# 3V3_REG.net
KiCad netlist of a schematic drawn in Altium Designer
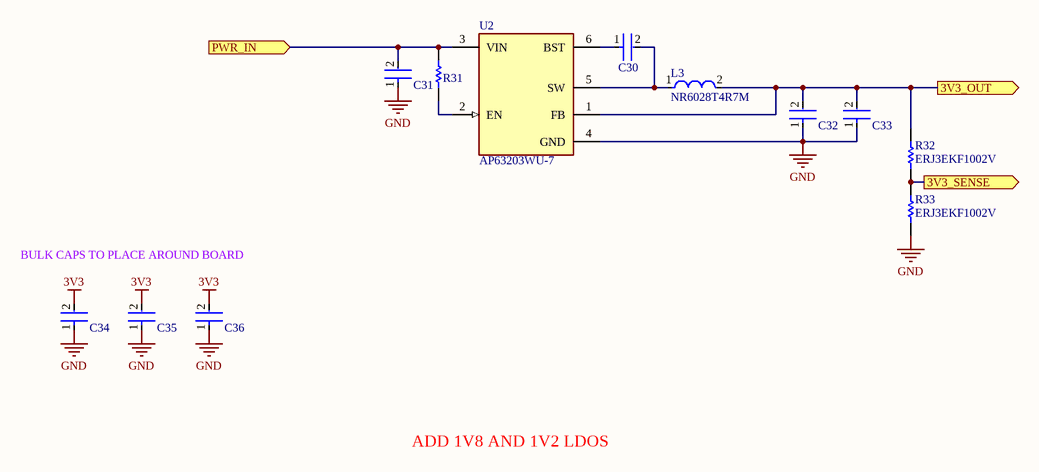
[diagram p0: 3V3_REG.SchDoc]

(export (version "E")
  (design (tool "Eeschema 10.0.6"))
  (components
    (comp (ref "C30")
      (value "C1005X7R1H104K050BB")
      (footprint "FP-C1005-050-0_05-IPC_C")
      (description "Multilayer Ceramic Capacitors 100nF ±10% 50V X7R SMD 0402")
      (fields (field (name "VOLTAGE") "50V") (field (name "TOLERANCE") "10%"))
      (libsource (lib "Altium Content Vault") (part "b4654b650e69147ec39a6b967a45e02"))
    )
    (comp (ref "C31")
      (value "GRM21BR61E226ME44L")
      (footprint "FP-GRM21B-0_2-e0_2_0_7-IPC_B")
      (description "Chip Multilayer Ceramic Capacitors for General Purpose, 0805, 22uF, X5R, 15%, 20%, 25V")
      (fields (field (name "TOLERANCE") "20%") (field (name "VOLTAGE") "25V"))
      (libsource (lib "Altium Content Vault") (part "b4654b650e69147ec39a6b967a45e02"))
    )
    (comp (ref "C32")
      (value "GRM21BR61E226ME44L")
      (footprint "FP-GRM21B-0_2-e0_2_0_7-IPC_B")
      (description "Chip Multilayer Ceramic Capacitors for General Purpose, 0805, 22uF, X5R, 15%, 20%, 25V")
      (fields (field (name "TOLERANCE") "20%") (field (name "VOLTAGE") "25V"))
      (libsource (lib "Altium Content Vault") (part "b4654b650e69147ec39a6b967a45e02"))
    )
    (comp (ref "C33")
      (value "GRM21BR61E226ME44L")
      (footprint "FP-GRM21B-0_2-e0_2_0_7-IPC_B")
      (description "Chip Multilayer Ceramic Capacitors for General Purpose, 0805, 22uF, X5R, 15%, 20%, 25V")
      (fields (field (name "TOLERANCE") "20%") (field (name "VOLTAGE") "25V"))
      (libsource (lib "Altium Content Vault") (part "b4654b650e69147ec39a6b967a45e02"))
    )
    (comp (ref "C34")
      (value "GRM21BR61E226ME44L")
      (footprint "FP-GRM21B-0_2-e0_2_0_7-IPC_B")
      (description "Chip Multilayer Ceramic Capacitors for General Purpose, 0805, 22uF, X5R, 15%, 20%, 25V")
      (fields (field (name "TOLERANCE") "20%") (field (name "VOLTAGE") "25V"))
      (libsource (lib "Altium Content Vault") (part "b4654b650e69147ec39a6b967a45e02"))
    )
    (comp (ref "C35")
      (value "GRM21BR61E226ME44L")
      (footprint "FP-GRM21B-0_2-e0_2_0_7-IPC_B")
      (description "Chip Multilayer Ceramic Capacitors for General Purpose, 0805, 22uF, X5R, 15%, 20%, 25V")
      (fields (field (name "TOLERANCE") "20%") (field (name "VOLTAGE") "25V"))
      (libsource (lib "Altium Content Vault") (part "b4654b650e69147ec39a6b967a45e02"))
    )
    (comp (ref "C36")
      (value "GRM21BR61E226ME44L")
      (footprint "FP-GRM21B-0_2-e0_2_0_7-IPC_B")
      (description "Chip Multilayer Ceramic Capacitors for General Purpose, 0805, 22uF, X5R, 15%, 20%, 25V")
      (fields (field (name "TOLERANCE") "20%") (field (name "VOLTAGE") "25V"))
      (libsource (lib "Altium Content Vault") (part "b4654b650e69147ec39a6b967a45e02"))
    )
    (comp (ref "L3")
      (value "NR6028T4R7M")
      (footprint "FP-NR6028-MFG")
      (description "SMD Power Inductors 4.7uH ±20% 2.7A 40.3mΩ")
      (fields (field (name "TOLERANCE") "20%"))
      (libsource (lib "Altium Content Vault") (part "725321dda6339637d4d059423bc1c3c"))
    )
    (comp (ref "R31")
      (value "RC0402JR-070RL")
      (footprint "RESC1005X40X25NL05T10")
      (fields (field (name "MANUFACTURER") "Yageo / Phycomp"))
      (libsource (lib "Altium Content Vault") (part "RES"))
    )
    (comp (ref "R32")
      (value "ERJ3EKF1002V")
      (footprint "RESC1609X55X30LL15T15")
      (description "Chip Resistor, 10 KOhm, +/- 1%, 0.1 W, -55 to 155 degC, 0603 (1608 Metric), RoHS, Tape and Reel")
      (fields (field (name "TOLERANCE") "1%") (field (name "MANUFACTURER") "Panasonic"))
      (libsource (lib "Altium Content Vault") (part "RES-2"))
    )
    (comp (ref "R33")
      (value "ERJ3EKF1002V")
      (footprint "RESC1609X55X30LL15T15")
      (description "Chip Resistor, 10 KOhm, +/- 1%, 0.1 W, -55 to 155 degC, 0603 (1608 Metric), RoHS, Tape and Reel")
      (fields (field (name "TOLERANCE") "1%") (field (name "MANUFACTURER") "Panasonic"))
      (libsource (lib "Altium Content Vault") (part "RES-2"))
    )
    (comp (ref "U2")
      (value "AP63203WU-7")
      (footprint "FP-TSOT26-MFG")
      (description "Buck Switching Regulator IC Positive Fixed 3.3V 1 Output 2A SOT-23-6 Thin, TSOT-23-6")
      (fields (field (name "MANUFACTURER") "Diodes Inc."))
      (libsource (lib "Altium Content Vault") (part "0e61c2974d7114b43f01ef96ae2e524"))
    )
  )
  (nets
    (net (code "1") (name "/3V3_OUT") (class "Default")
      (node (ref "C32") (pin "2") (pinfunction "2_2") (pintype "passive"))
      (node (ref "C33") (pin "2") (pinfunction "2_2") (pintype "passive"))
      (node (ref "L3") (pin "2") (pinfunction "2_2") (pintype "passive"))
      (node (ref "R32") (pin "2") (pinfunction "2_2") (pintype "passive"))
      (node (ref "U2") (pin "1") (pinfunction "FB_1") (pintype "passive"))
    )
    (net (code "2") (name "/3V3_SENSE") (class "Default")
      (node (ref "R32") (pin "1") (pinfunction "1_1") (pintype "passive"))
      (node (ref "R33") (pin "2") (pinfunction "2_2") (pintype "passive"))
    )
    (net (code "3") (name "/PWR_IN") (class "Default")
      (node (ref "C31") (pin "2") (pinfunction "2_2") (pintype "passive"))
      (node (ref "R31") (pin "2") (pinfunction "2_2") (pintype "passive"))
      (node (ref "U2") (pin "3") (pinfunction "VIN_3") (pintype "power_in"))
    )
    (net (code "4") (name "3V3") (class "Default")
      (node (ref "C34") (pin "2") (pinfunction "2_2") (pintype "passive"))
      (node (ref "C35") (pin "2") (pinfunction "2_2") (pintype "passive"))
      (node (ref "C36") (pin "2") (pinfunction "2_2") (pintype "passive"))
    )
    (net (code "5") (name "GND") (class "Default")
      (node (ref "C31") (pin "1") (pinfunction "1_1") (pintype "passive"))
      (node (ref "C32") (pin "1") (pinfunction "1_1") (pintype "passive"))
      (node (ref "C33") (pin "1") (pinfunction "1_1") (pintype "passive"))
      (node (ref "C34") (pin "1") (pinfunction "1_1") (pintype "passive"))
      (node (ref "C35") (pin "1") (pinfunction "1_1") (pintype "passive"))
      (node (ref "C36") (pin "1") (pinfunction "1_1") (pintype "passive"))
      (node (ref "R33") (pin "1") (pinfunction "1_1") (pintype "passive"))
      (node (ref "U2") (pin "4") (pinfunction "GND_4") (pintype "power_in"))
    )
    (net (code "6") (name "Net-(U2-BST)") (class "Default")
      (node (ref "C30") (pin "1") (pinfunction "1_1") (pintype "passive"))
      (node (ref "U2") (pin "6") (pinfunction "BST_6") (pintype "passive"))
    )
    (net (code "7") (name "Net-(U2-EN)") (class "Default")
      (node (ref "R31") (pin "1") (pinfunction "1_1") (pintype "passive"))
      (node (ref "U2") (pin "2") (pinfunction "EN_2") (pintype "input"))
    )
    (net (code "8") (name "Net-(U2-SW)") (class "Default")
      (node (ref "C30") (pin "2") (pinfunction "2_2") (pintype "passive"))
      (node (ref "L3") (pin "1") (pinfunction "1_1") (pintype "passive"))
      (node (ref "U2") (pin "5") (pinfunction "SW_5") (pintype "passive"))
    )
  )
)
